# Rocketometer2148_MPU9150_GPS_No_Osc.net
KiCad netlist of a schematic drawn in EAGLE
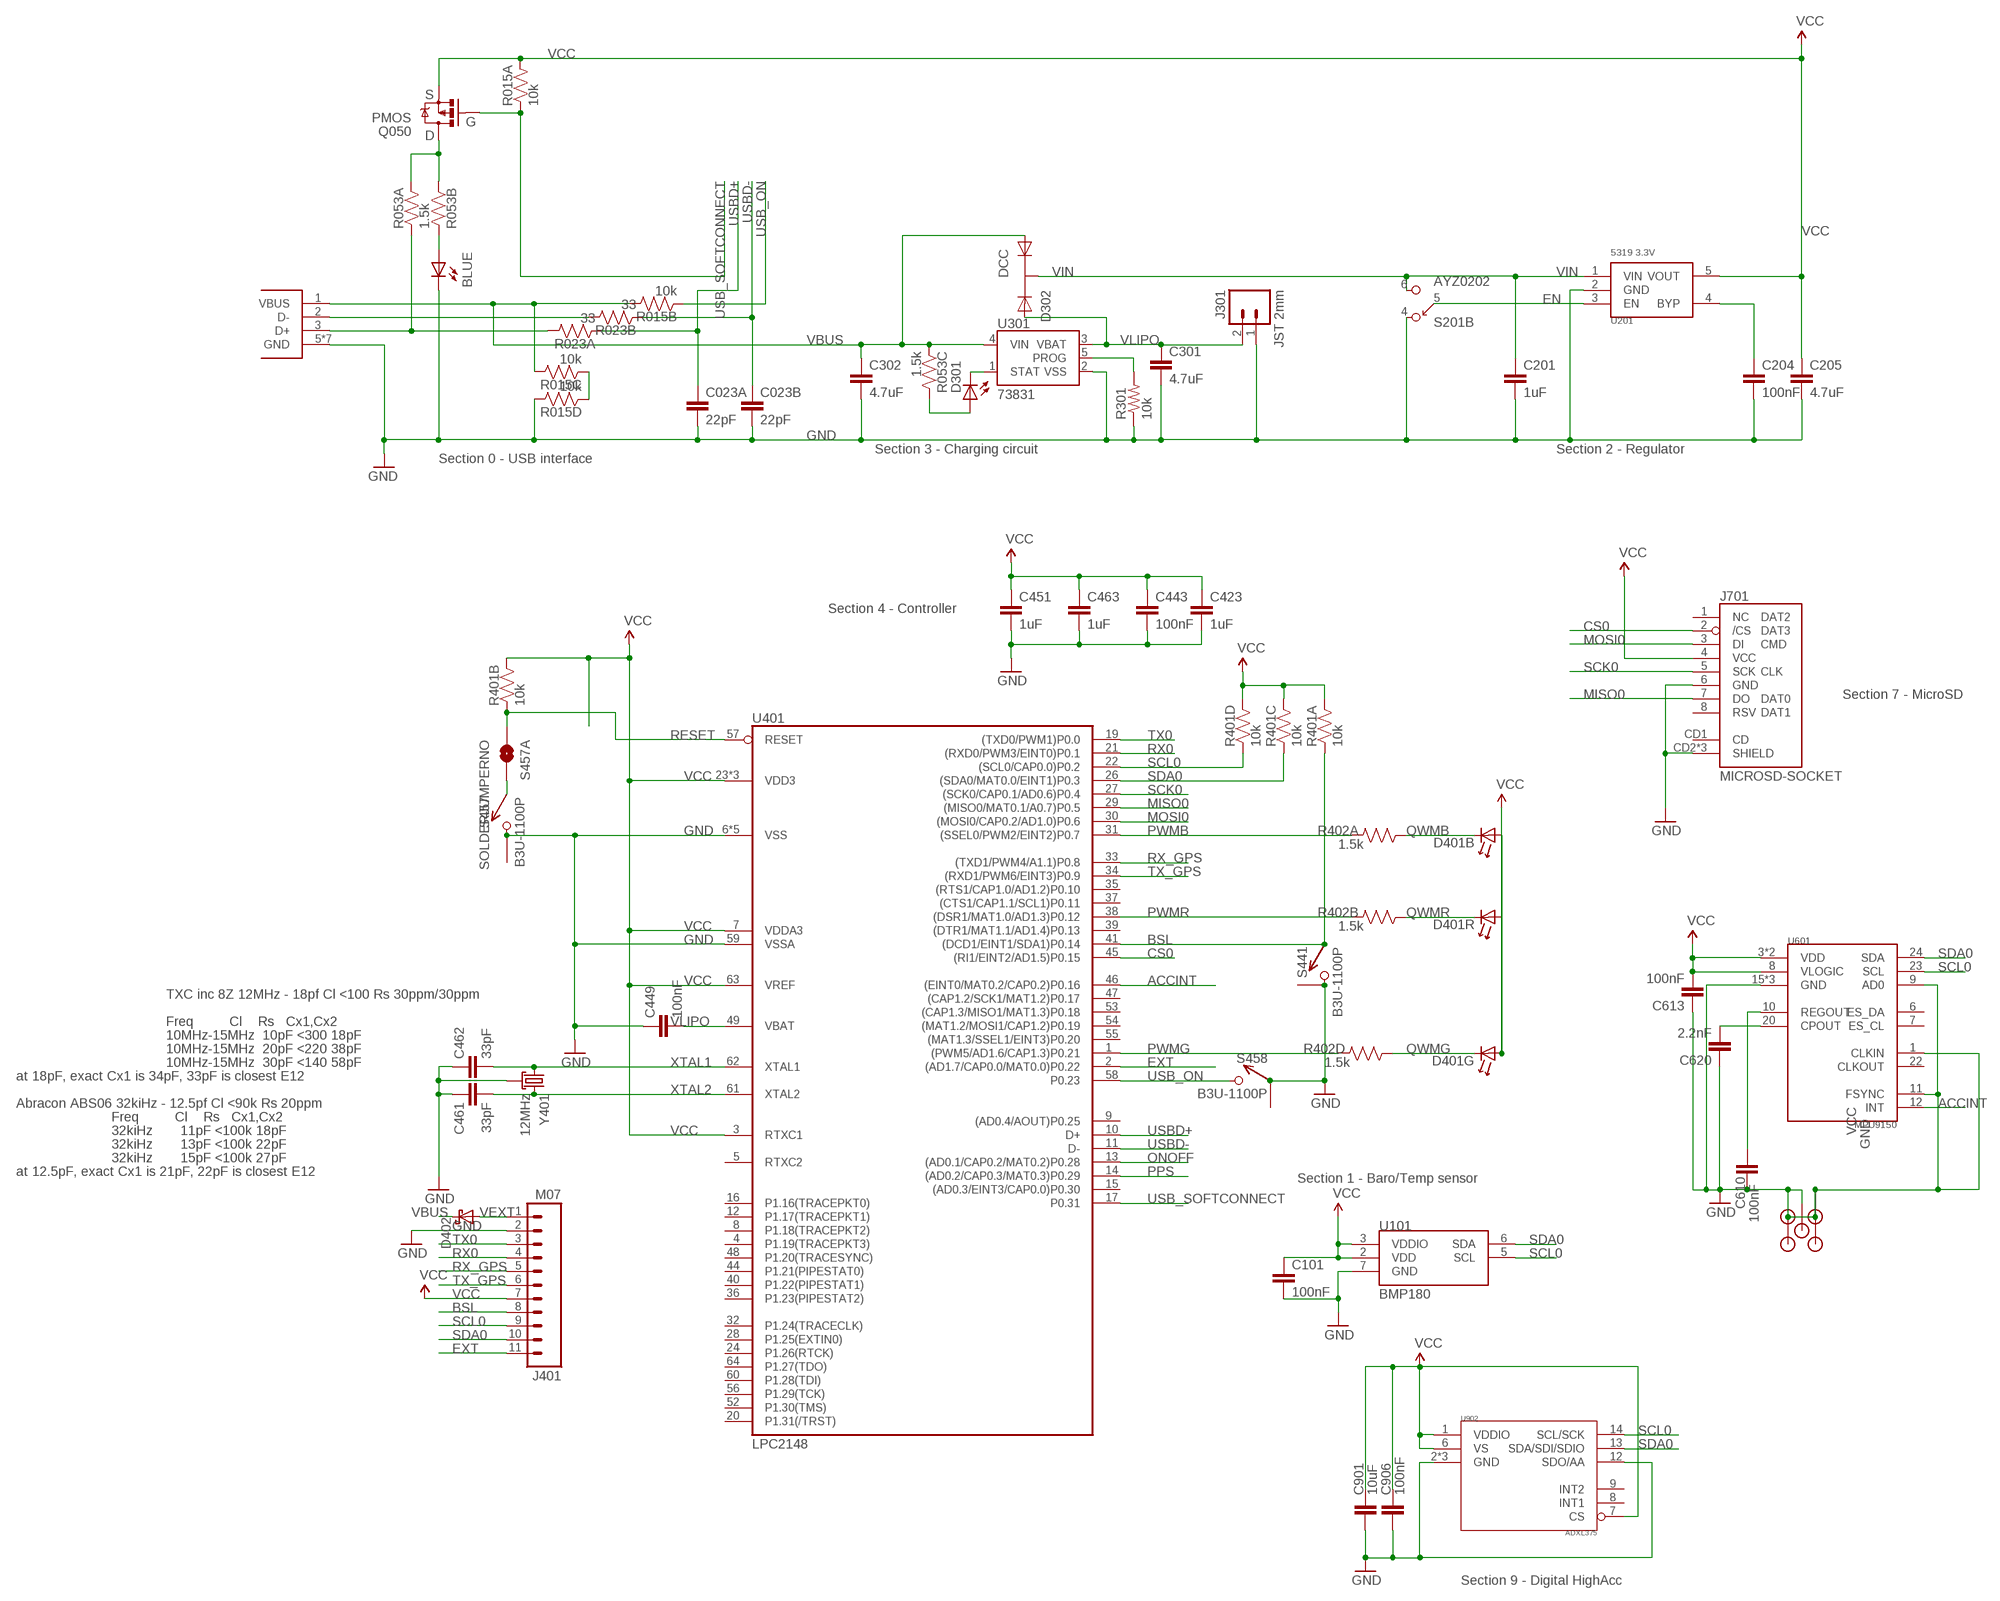
[diagram p0: schematic, sheet 1, part 1 of 2]
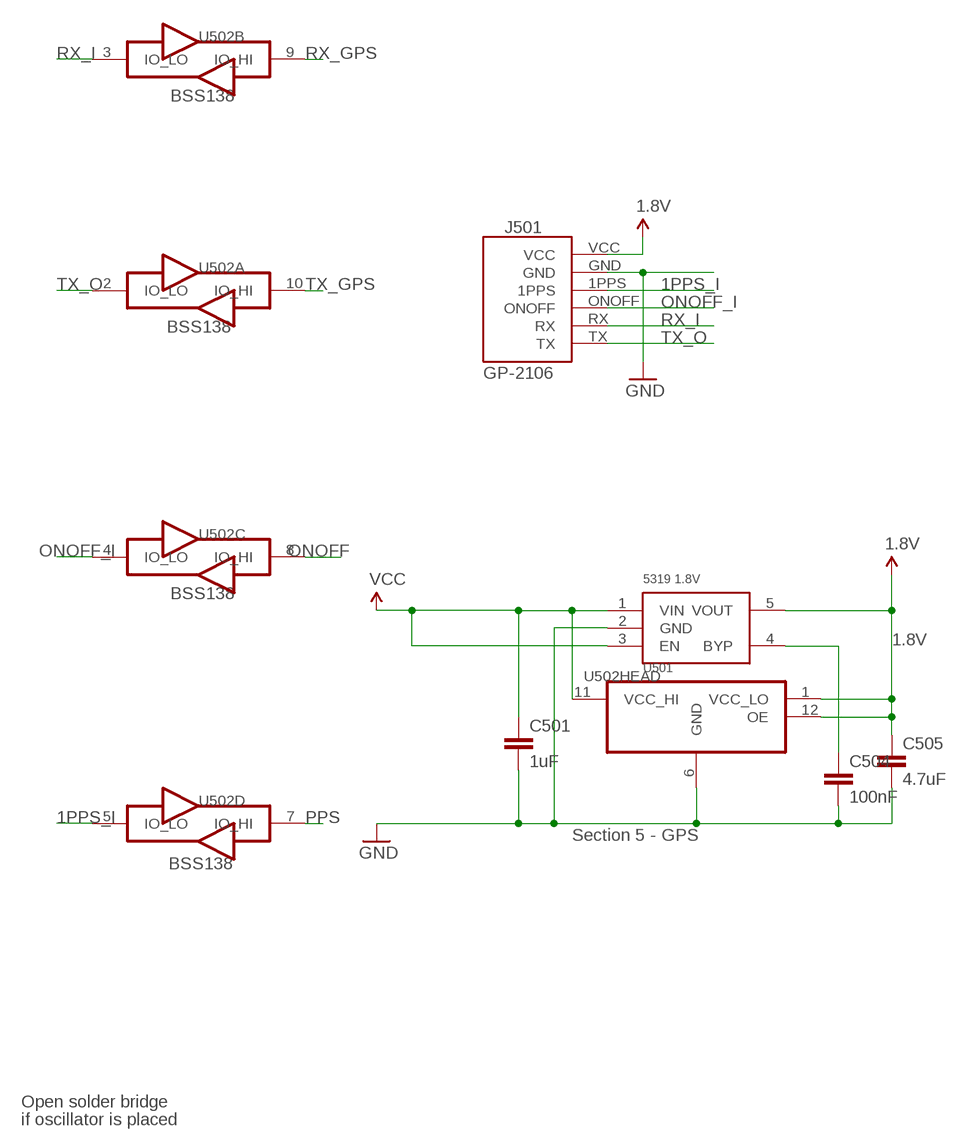
[diagram p1: schematic, sheet 1, part 2 of 2]

(export (version "E")
  (design (tool "Eeschema 10.0.6"))
  (components
    (comp (ref "C023")
      (value "22pF")
      (footprint "eagle-import:CKCM25")
      (fields (field (name "DIGIKEY") "445-1860-1-ND"))
      (libsource (lib "eagle-import") (part "CKCM25"))
    )
    (comp (ref "C101")
      (value "100nF")
      (footprint "eagle-import:0402-CAP")
      (libsource (lib "eagle-import") (part "CAP0402-CAP"))
    )
    (comp (ref "C201")
      (value "1uF")
      (footprint "eagle-import:0402-CAP")
      (libsource (lib "eagle-import") (part "CAP0402-CAP"))
    )
    (comp (ref "C204")
      (value "100nF")
      (footprint "eagle-import:0402-CAP")
      (libsource (lib "eagle-import") (part "CAP0402-CAP"))
    )
    (comp (ref "C205")
      (value "4.7uF")
      (footprint "eagle-import:0402-CAP")
      (libsource (lib "eagle-import") (part "CAP0402-CAP"))
    )
    (comp (ref "C301")
      (value "4.7uF")
      (footprint "eagle-import:0402-CAP")
      (libsource (lib "eagle-import") (part "CAP0402-CAP"))
    )
    (comp (ref "C302")
      (value "4.7uF")
      (footprint "eagle-import:0402-CAP")
      (libsource (lib "eagle-import") (part "CAP0402-CAP"))
    )
    (comp (ref "C423")
      (value "1uF")
      (footprint "eagle-import:0402-CAP")
      (libsource (lib "eagle-import") (part "CAP0402-CAP"))
    )
    (comp (ref "C443")
      (value "100nF")
      (footprint "eagle-import:0402-CAP")
      (libsource (lib "eagle-import") (part "CAP0402-CAP"))
    )
    (comp (ref "C449")
      (value "100nF")
      (footprint "eagle-import:0402-CAP")
      (libsource (lib "eagle-import") (part "CAP0402-CAP"))
    )
    (comp (ref "C451")
      (value "1uF")
      (footprint "eagle-import:0402-CAP")
      (libsource (lib "eagle-import") (part "CAP0402-CAP"))
    )
    (comp (ref "C461")
      (value "33pF")
      (footprint "eagle-import:0402-CAP")
      (libsource (lib "eagle-import") (part "CAP0402-CAP"))
    )
    (comp (ref "C462")
      (value "33pF")
      (footprint "eagle-import:0402-CAP")
      (libsource (lib "eagle-import") (part "CAP0402-CAP"))
    )
    (comp (ref "C463")
      (value "1uF")
      (footprint "eagle-import:0402-CAP")
      (libsource (lib "eagle-import") (part "CAP0402-CAP"))
    )
    (comp (ref "C501")
      (value "1uF")
      (footprint "eagle-import:0402-CAP")
      (libsource (lib "eagle-import") (part "CAP0402-CAP"))
    )
    (comp (ref "C504")
      (value "100nF")
      (footprint "eagle-import:0402-CAP")
      (libsource (lib "eagle-import") (part "CAP0402-CAP"))
    )
    (comp (ref "C505")
      (value "4.7uF")
      (footprint "eagle-import:0402-CAP")
      (libsource (lib "eagle-import") (part "CAP0402-CAP"))
    )
    (comp (ref "C610")
      (value "100nF")
      (footprint "eagle-import:0402-CAP")
      (libsource (lib "eagle-import") (part "CAP0402-CAP"))
    )
    (comp (ref "C613")
      (value "100nF")
      (footprint "eagle-import:0402-CAP")
      (libsource (lib "eagle-import") (part "CAP0402-CAP"))
    )
    (comp (ref "C620")
      (value "2.2nF")
      (footprint "eagle-import:0402-CAP")
      (libsource (lib "eagle-import") (part "CAP0402-CAP"))
    )
    (comp (ref "C901")
      (value "10uF")
      (footprint "eagle-import:0603-CAP")
      (libsource (lib "eagle-import") (part "CAP0603-CAP"))
    )
    (comp (ref "C906")
      (value "100nF")
      (footprint "eagle-import:0402-CAP")
      (libsource (lib "eagle-import") (part "SparkFun-Passives_CAP0402-CAP"))
    )
    (comp (ref "D050")
      (value "BLUE")
      (footprint "eagle-import:LED-0603")
      (libsource (lib "eagle-import") (part "LED0603"))
    )
    (comp (ref "D301")
      (value "YELLOW")
      (footprint "eagle-import:LED-0603")
      (libsource (lib "eagle-import") (part "LED0603"))
    )
    (comp (ref "D302")
      (value "DCC")
      (footprint "eagle-import:SOT-23-3")
      (libsource (lib "eagle-import") (part "PMEG2005CT"))
    )
    (comp (ref "D401")
      (value "SMLP36RGB2W(R)")
      (footprint "eagle-import:SMLP36")
      (fields (field (name "DIGIKEY") "846-1097-1-ND"))
      (libsource (lib "eagle-import") (part "SMLP36RGB2W(R)"))
    )
    (comp (ref "D402")
      (value "DIODE_SCHOTTKY")
      (footprint "eagle-import:D0603")
      (libsource (lib "eagle-import") (part "DIODE_SCHOTTKY"))
    )
    (comp (ref "J001")
      (value "USB_MICROB_JSTGCT")
      (footprint "eagle-import:USB_MICROB_3075")
      (libsource (lib "eagle-import") (part "USB_MICROB_JSTGCT"))
    )
    (comp (ref "J301")
      (value "JST 2mm")
      (footprint "eagle-import:JST-2-SMD")
      (libsource (lib "eagle-import") (part "M02-JST-2MM-SMT"))
    )
    (comp (ref "J401")
      (value "M07")
      (footprint "eagle-import:1X11")
      (libsource (lib "eagle-import") (part "M11PTH"))
    )
    (comp (ref "J501")
      (value "GP-2106")
      (footprint "eagle-import:GP-2106")
      (libsource (lib "eagle-import") (part "GP-2106"))
    )
    (comp (ref "J701")
      (value "MICROSD-SOCKET")
      (footprint "eagle-import:MICROSD-SOCKET-PP")
      (libsource (lib "eagle-import") (part "MICROSD-SOCKET"))
    )
    (comp (ref "JP1")
      (value "STANDOFF")
      (footprint "eagle-import:STANDOFF")
      (libsource (lib "eagle-import") (part "STANDOFF"))
    )
    (comp (ref "JP2")
      (value "STANDOFF")
      (footprint "eagle-import:STANDOFF")
      (libsource (lib "eagle-import") (part "STANDOFF"))
    )
    (comp (ref "JP3")
      (value "STANDOFF")
      (footprint "eagle-import:STANDOFF")
      (libsource (lib "eagle-import") (part "STANDOFF"))
    )
    (comp (ref "JP4")
      (value "STANDOFF")
      (footprint "eagle-import:STANDOFF")
      (libsource (lib "eagle-import") (part "STANDOFF"))
    )
    (comp (ref "JP5")
      (value "STANDOFF")
      (footprint "eagle-import:STANDOFF")
      (libsource (lib "eagle-import") (part "STANDOFF"))
    )
    (comp (ref "Q050")
      (value "PMOS")
      (footprint "eagle-import:SOT23-3")
      (libsource (lib "eagle-import") (part "MOSFET-PCHANNELSMD"))
    )
    (comp (ref "R015")
      (value "10k")
      (footprint "eagle-import:CRA04")
      (fields (field (name "DIGIKEY") "Y5103CT-ND"))
      (libsource (lib "eagle-import") (part "RP404"))
    )
    (comp (ref "R023")
      (value "33")
      (footprint "eagle-import:CRA02")
      (libsource (lib "eagle-import") (part "RP2EXB24V"))
    )
    (comp (ref "R053")
      (value "1.5k")
      (footprint "eagle-import:CRA04")
      (fields (field (name "DIGIKEY") "CRA4S81.5KCT-ND"))
      (libsource (lib "eagle-import") (part "RP404"))
    )
    (comp (ref "R301")
      (value "10k")
      (footprint "eagle-import:0402-RES")
      (libsource (lib "eagle-import") (part "RESISTOR0402-RES"))
    )
    (comp (ref "R401")
      (value "10k")
      (footprint "eagle-import:CRA04")
      (fields (field (name "DIGIKEY") "CRA4S810KCT-ND"))
      (libsource (lib "eagle-import") (part "RP404"))
    )
    (comp (ref "R402")
      (value "1.5k")
      (footprint "eagle-import:CRA04")
      (fields (field (name "DIGIKEY") "CRA4S81.5KCT-ND"))
      (libsource (lib "eagle-import") (part "RP404"))
    )
    (comp (ref "S201")
      (value "AYZ0202")
      (footprint "eagle-import:AYZ0202")
      (libsource (lib "eagle-import") (part "AYZ0202"))
    )
    (comp (ref "S441")
      (value "B3U-1100P")
      (footprint "eagle-import:B3U-1100P")
      (fields (field (name "DIGIKEY") "SW1021CT-ND"))
      (libsource (lib "eagle-import") (part "B3U-1100P"))
    )
    (comp (ref "S457")
      (value "B3U-1100P")
      (footprint "eagle-import:B3U-1100P")
      (fields (field (name "DIGIKEY") "SW1021CT-ND"))
      (libsource (lib "eagle-import") (part "B3U-1100P"))
    )
    (comp (ref "S457A")
      (value "SOLDERJUMPERNO")
      (footprint "eagle-import:SJ_2S-NO")
      (libsource (lib "eagle-import") (part "SOLDERJUMPERNO"))
    )
    (comp (ref "S458")
      (value "B3U-1100P")
      (footprint "eagle-import:B3U-1100P")
      (fields (field (name "DIGIKEY") "SW1021CT-ND"))
      (libsource (lib "eagle-import") (part "B3U-1100P"))
    )
    (comp (ref "U101")
      (value "BMP180")
      (footprint "eagle-import:BMP180")
      (libsource (lib "eagle-import") (part "BMP180"))
    )
    (comp (ref "U201")
      (value "5319 3.3V")
      (footprint "eagle-import:SOT-23-5")
      (libsource (lib "eagle-import") (part "MIC5319D5"))
    )
    (comp (ref "U301")
      (value "73831")
      (footprint "eagle-import:SOT23-5")
      (libsource (lib "eagle-import") (part "MCP73831"))
    )
    (comp (ref "U401")
      (value "LPC2148")
      (footprint "eagle-import:LQFP64")
      (libsource (lib "eagle-import") (part "LPC2148"))
    )
    (comp (ref "U501")
      (value "5319 1.8V")
      (footprint "eagle-import:SOT-23-5")
      (libsource (lib "eagle-import") (part "MIC5319D5"))
    )
    (comp (ref "U502")
      (value "TXB0104RUT")
      (footprint "eagle-import:R-PUQFN-N12")
      (libsource (lib "eagle-import") (part "TXB0104RUT"))
    )
    (comp (ref "U601")
      (value "MPU9150")
      (footprint "eagle-import:LLGA24")
      (libsource (lib "eagle-import") (part "MPU9150"))
    )
    (comp (ref "U902")
      (value "ADXL375")
      (footprint "eagle-import:ADXL375")
      (libsource (lib "eagle-import") (part "ADXL375"))
    )
    (comp (ref "Y401")
      (value "12MHz")
      (footprint "eagle-import:CRYSTAL_SMD_2MM_2_5MM")
      (libsource (lib "eagle-import") (part "CX2520"))
    )
  )
  (nets
    (net (code "1") (name "/1PPS_I") (class "Default")
      (node (ref "J501") (pin "1PPS") (pinfunction "1PPS_1PPS") (pintype "bidirectional"))
      (node (ref "U502") (pin "5") (pinfunction "IO_LO_5") (pintype "bidirectional"))
    )
    (net (code "2") (name "/ACCINT") (class "Default")
      (node (ref "U401") (pin "46") (pinfunction "(EINT0/MAT0.2/CAP0.2)P0.16_46") (pintype "bidirectional"))
      (node (ref "U601") (pin "12") (pinfunction "INT_12") (pintype "bidirectional"))
    )
    (net (code "3") (name "/BSL") (class "Default")
      (node (ref "J401") (pin "8") (pinfunction "8_8") (pintype "passive"))
      (node (ref "R401") (pin "1") (pinfunction "1_1") (pintype "passive"))
      (node (ref "S441") (pin "P$1") (pinfunction "1_P$1") (pintype "bidirectional"))
      (node (ref "U401") (pin "41") (pinfunction "(DCD1/EINT1/SDA1)P0.14_41") (pintype "bidirectional"))
    )
    (net (code "4") (name "/CS0") (class "Default")
      (node (ref "J701") (pin "2") (pinfunction "/CS_2") (pintype "bidirectional"))
      (node (ref "U401") (pin "45") (pinfunction "(RI1/EINT2/AD1.5)P0.15_45") (pintype "bidirectional"))
    )
    (net (code "5") (name "/EN") (class "Default")
      (node (ref "S201") (pin "5") (pinfunction "P$3_5") (pintype "bidirectional"))
      (node (ref "U201") (pin "3") (pinfunction "EN_3") (pintype "bidirectional"))
    )
    (net (code "6") (name "/EXT") (class "Default")
      (node (ref "J401") (pin "11") (pinfunction "11_11") (pintype "passive"))
      (node (ref "U401") (pin "2") (pinfunction "(AD1.7/CAP0.0/MAT0.0)P0.22_2") (pintype "bidirectional"))
    )
    (net (code "7") (name "/MISO0") (class "Default")
      (node (ref "J701") (pin "7") (pinfunction "DO_7") (pintype "bidirectional"))
      (node (ref "U401") (pin "29") (pinfunction "(MISO0/MAT0.1/A0.7)P0.5_29") (pintype "bidirectional"))
    )
    (net (code "8") (name "/MOSI0") (class "Default")
      (node (ref "J701") (pin "3") (pinfunction "DI_3") (pintype "bidirectional"))
      (node (ref "U401") (pin "30") (pinfunction "(MOSI0/CAP0.2/AD1.0)P0.6_30") (pintype "bidirectional"))
    )
    (net (code "9") (name "/ONOFF") (class "Default")
      (node (ref "U401") (pin "13") (pinfunction "(AD0.1/CAP0.2/MAT0.2)P0.28_13") (pintype "bidirectional"))
      (node (ref "U502") (pin "8") (pinfunction "IO_HI_8") (pintype "bidirectional"))
    )
    (net (code "10") (name "/ONOFF_I") (class "Default")
      (node (ref "J501") (pin "ONOFF") (pinfunction "ONOFF_ONOFF") (pintype "bidirectional"))
      (node (ref "U502") (pin "4") (pinfunction "IO_LO_4") (pintype "bidirectional"))
    )
    (net (code "11") (name "/PPS") (class "Default")
      (node (ref "U401") (pin "14") (pinfunction "(AD0.2/CAP0.3/MAT0.3)P0.29_14") (pintype "bidirectional"))
      (node (ref "U502") (pin "7") (pinfunction "IO_HI_7") (pintype "bidirectional"))
    )
    (net (code "12") (name "/PWMB") (class "Default")
      (node (ref "R402") (pin "8") (pinfunction "2_8") (pintype "passive"))
      (node (ref "U401") (pin "31") (pinfunction "(SSEL0/PWM2/EINT2)P0.7_31") (pintype "bidirectional"))
    )
    (net (code "13") (name "/PWMG") (class "Default")
      (node (ref "R402") (pin "5") (pinfunction "2_5") (pintype "passive"))
      (node (ref "U401") (pin "1") (pinfunction "(PWM5/AD1.6/CAP1.3)P0.21_1") (pintype "bidirectional"))
    )
    (net (code "14") (name "/PWMR") (class "Default")
      (node (ref "R402") (pin "7") (pinfunction "2_7") (pintype "passive"))
      (node (ref "U401") (pin "38") (pinfunction "(DSR1/MAT1.0/AD1.3)P0.12_38") (pintype "bidirectional"))
    )
    (net (code "15") (name "/QWMB") (class "Default")
      (node (ref "D401") (pin "1") (pinfunction "C_1") (pintype "passive"))
      (node (ref "R402") (pin "1") (pinfunction "1_1") (pintype "passive"))
    )
    (net (code "16") (name "/QWMG") (class "Default")
      (node (ref "D401") (pin "5") (pinfunction "C_5") (pintype "passive"))
      (node (ref "R402") (pin "4") (pinfunction "1_4") (pintype "passive"))
    )
    (net (code "17") (name "/QWMR") (class "Default")
      (node (ref "D401") (pin "3") (pinfunction "C_3") (pintype "passive"))
      (node (ref "R402") (pin "2") (pinfunction "1_2") (pintype "passive"))
    )
    (net (code "18") (name "/RESET") (class "Default")
      (node (ref "R401") (pin "2") (pinfunction "1_2") (pintype "passive"))
      (node (ref "S457A") (pin "1") (pinfunction "1_1") (pintype "passive"))
      (node (ref "U401") (pin "57") (pinfunction "RESET_57") (pintype "input"))
    )
    (net (code "19") (name "/RX0") (class "Default")
      (node (ref "J401") (pin "4") (pinfunction "4_4") (pintype "passive"))
      (node (ref "U401") (pin "21") (pinfunction "(RXD0/PWM3/EINT0)P0.1_21") (pintype "bidirectional"))
    )
    (net (code "20") (name "/RX_GPS") (class "Default")
      (node (ref "J401") (pin "5") (pinfunction "5_5") (pintype "passive"))
      (node (ref "U401") (pin "33") (pinfunction "(TXD1/PWM4/A1.1)P0.8_33") (pintype "bidirectional"))
      (node (ref "U502") (pin "9") (pinfunction "IO_HI_9") (pintype "bidirectional"))
    )
    (net (code "21") (name "/RX_I") (class "Default")
      (node (ref "J501") (pin "RX") (pinfunction "RX_RX") (pintype "bidirectional"))
      (node (ref "U502") (pin "3") (pinfunction "IO_LO_3") (pintype "bidirectional"))
    )
    (net (code "22") (name "/SCK0") (class "Default")
      (node (ref "J701") (pin "5") (pinfunction "SCK_5") (pintype "bidirectional"))
      (node (ref "U401") (pin "27") (pinfunction "(SCK0/CAP0.1/AD0.6)P0.4_27") (pintype "bidirectional"))
    )
    (net (code "23") (name "/SCL0") (class "Default")
      (node (ref "J401") (pin "9") (pinfunction "9_9") (pintype "passive"))
      (node (ref "R401") (pin "4") (pinfunction "1_4") (pintype "passive"))
      (node (ref "U101") (pin "5") (pinfunction "SCL_5") (pintype "input"))
      (node (ref "U401") (pin "22") (pinfunction "(SCL0/CAP0.0)P0.2_22") (pintype "bidirectional"))
      (node (ref "U601") (pin "23") (pinfunction "SCL_23") (pintype "bidirectional"))
      (node (ref "U902") (pin "14") (pinfunction "SCL/SCK_14") (pintype "input"))
    )
    (net (code "24") (name "/SDA0") (class "Default")
      (node (ref "J401") (pin "10") (pinfunction "10_10") (pintype "passive"))
      (node (ref "R401") (pin "3") (pinfunction "1_3") (pintype "passive"))
      (node (ref "U101") (pin "6") (pinfunction "SDA_6") (pintype "bidirectional"))
      (node (ref "U401") (pin "26") (pinfunction "(SDA0/MAT0.0/EINT1)P0.3_26") (pintype "bidirectional"))
      (node (ref "U601") (pin "24") (pinfunction "SDA_24") (pintype "bidirectional"))
      (node (ref "U902") (pin "13") (pinfunction "SDA/SDI/SDIO_13") (pintype "bidirectional"))
    )
    (net (code "25") (name "/TX0") (class "Default")
      (node (ref "J401") (pin "3") (pinfunction "3_3") (pintype "passive"))
      (node (ref "U401") (pin "19") (pinfunction "(TXD0/PWM1)P0.0_19") (pintype "bidirectional"))
    )
    (net (code "26") (name "/TX_GPS") (class "Default")
      (node (ref "J401") (pin "6") (pinfunction "6_6") (pintype "passive"))
      (node (ref "U401") (pin "34") (pinfunction "(RXD1/PWM6/EINT3)P0.9_34") (pintype "bidirectional"))
      (node (ref "U502") (pin "10") (pinfunction "IO_HI_10") (pintype "bidirectional"))
    )
    (net (code "27") (name "/TX_O") (class "Default")
      (node (ref "J501") (pin "TX") (pinfunction "TX_TX") (pintype "bidirectional"))
      (node (ref "U502") (pin "2") (pinfunction "IO_LO_2") (pintype "bidirectional"))
    )
    (net (code "28") (name "/USBD+") (class "Default")
      (node (ref "C023") (pin "1") (pinfunction "1_1") (pintype "passive"))
      (node (ref "R023") (pin "1") (pinfunction "1_1") (pintype "passive"))
      (node (ref "U401") (pin "10") (pinfunction "D+_10") (pintype "bidirectional"))
    )
    (net (code "29") (name "/USBD-") (class "Default")
      (node (ref "C023") (pin "2") (pinfunction "1_2") (pintype "passive"))
      (node (ref "R023") (pin "2") (pinfunction "1_2") (pintype "passive"))
      (node (ref "U401") (pin "11") (pinfunction "D-_11") (pintype "bidirectional"))
    )
    (net (code "30") (name "/USB_ON") (class "Default")
      (node (ref "R015") (pin "2") (pinfunction "1_2") (pintype "passive"))
      (node (ref "S458") (pin "P$2") (pinfunction "2_P$2") (pintype "bidirectional"))
      (node (ref "U401") (pin "58") (pinfunction "P0.23_58") (pintype "bidirectional"))
    )
    (net (code "31") (name "/USB_SOFTCONNECT") (class "Default")
      (node (ref "Q050") (pin "1") (pinfunction "G_1") (pintype "passive"))
      (node (ref "R015") (pin "1") (pinfunction "1_1") (pintype "passive"))
      (node (ref "U401") (pin "17") (pinfunction "P0.31_17") (pintype "output"))
    )
    (net (code "32") (name "/VBUS") (class "Default")
      (node (ref "C302") (pin "1") (pinfunction "1_1") (pintype "passive"))
      (node (ref "D302") (pin "1") (pinfunction "A1_1") (pintype "passive"))
      (node (ref "D402") (pin "C") (pinfunction "K_C") (pintype "passive"))
      (node (ref "J001") (pin "1") (pinfunction "VBUS_1") (pintype "bidirectional"))
      (node (ref "R015") (pin "6") (pinfunction "2_6") (pintype "passive"))
      (node (ref "R015") (pin "7") (pinfunction "2_7") (pintype "passive"))
      (node (ref "R053") (pin "3") (pinfunction "1_3") (pintype "passive"))
      (node (ref "U301") (pin "4") (pinfunction "VIN_4") (pintype "power_in"))
    )
    (net (code "33") (name "/VEXT") (class "Default")
      (node (ref "D402") (pin "A") (pinfunction "A_A") (pintype "passive"))
      (node (ref "J401") (pin "1") (pinfunction "1_1") (pintype "passive"))
    )
    (net (code "34") (name "/VIN") (class "Default")
      (node (ref "C201") (pin "1") (pinfunction "1_1") (pintype "passive"))
      (node (ref "D302") (pin "3") (pinfunction "K_3") (pintype "passive"))
      (node (ref "S201") (pin "6") (pinfunction "P$2_6") (pintype "bidirectional"))
      (node (ref "U201") (pin "1") (pinfunction "VIN_1") (pintype "bidirectional"))
    )
    (net (code "35") (name "/VLIPO") (class "Default")
      (node (ref "C301") (pin "1") (pinfunction "1_1") (pintype "passive"))
      (node (ref "C449") (pin "2") (pinfunction "2_2") (pintype "passive"))
      (node (ref "D302") (pin "2") (pinfunction "A2_2") (pintype "passive"))
      (node (ref "J301") (pin "2") (pinfunction "2_2") (pintype "passive"))
      (node (ref "U301") (pin "3") (pinfunction "VBAT_3") (pintype "power_in"))
      (node (ref "U401") (pin "49") (pinfunction "VBAT_49") (pintype "power_in"))
    )
    (net (code "36") (name "/XTAL1") (class "Default")
      (node (ref "C462") (pin "2") (pinfunction "2_2") (pintype "passive"))
      (node (ref "U401") (pin "62") (pinfunction "XTAL1_62") (pintype "input"))
      (node (ref "Y401") (pin "1") (pinfunction "1_1") (pintype "passive"))
    )
    (net (code "37") (name "/XTAL2") (class "Default")
      (node (ref "C461") (pin "2") (pinfunction "2_2") (pintype "passive"))
      (node (ref "U401") (pin "61") (pinfunction "XTAL2_61") (pintype "output"))
      (node (ref "Y401") (pin "3") (pinfunction "2_3") (pintype "passive"))
    )
    (net (code "38") (name "1.8V") (class "Default")
      (node (ref "C505") (pin "1") (pinfunction "1_1") (pintype "passive"))
      (node (ref "J501") (pin "VCC") (pinfunction "VCC_VCC") (pintype "bidirectional"))
      (node (ref "U501") (pin "5") (pinfunction "VOUT_5") (pintype "bidirectional"))
      (node (ref "U502") (pin "1") (pinfunction "VCC_LO_1") (pintype "power_in"))
      (node (ref "U502") (pin "12") (pinfunction "OE_12") (pintype "bidirectional"))
    )
    (net (code "39") (name "GND") (class "Default")
      (node (ref "C023") (pin "3") (pinfunction "2_3") (pintype "passive"))
      (node (ref "C023") (pin "4") (pinfunction "2_4") (pintype "passive"))
      (node (ref "C101") (pin "2") (pinfunction "2_2") (pintype "passive"))
      (node (ref "C201") (pin "2") (pinfunction "2_2") (pintype "passive"))
      (node (ref "C204") (pin "2") (pinfunction "2_2") (pintype "passive"))
      (node (ref "C205") (pin "2") (pinfunction "2_2") (pintype "passive"))
      (node (ref "C301") (pin "2") (pinfunction "2_2") (pintype "passive"))
      (node (ref "C302") (pin "2") (pinfunction "2_2") (pintype "passive"))
      (node (ref "C423") (pin "2") (pinfunction "2_2") (pintype "passive"))
      (node (ref "C443") (pin "2") (pinfunction "2_2") (pintype "passive"))
      (node (ref "C449") (pin "1") (pinfunction "1_1") (pintype "passive"))
      (node (ref "C451") (pin "2") (pinfunction "2_2") (pintype "passive"))
      (node (ref "C461") (pin "1") (pinfunction "1_1") (pintype "passive"))
      (node (ref "C462") (pin "1") (pinfunction "1_1") (pintype "passive"))
      (node (ref "C463") (pin "2") (pinfunction "2_2") (pintype "passive"))
      (node (ref "C501") (pin "2") (pinfunction "2_2") (pintype "passive"))
      (node (ref "C504") (pin "2") (pinfunction "2_2") (pintype "passive"))
      (node (ref "C505") (pin "2") (pinfunction "2_2") (pintype "passive"))
      (node (ref "C610") (pin "2") (pinfunction "2_2") (pintype "passive"))
      (node (ref "C613") (pin "1") (pinfunction "1_1") (pintype "passive"))
      (node (ref "C620") (pin "1") (pinfunction "1_1") (pintype "passive"))
      (node (ref "C901") (pin "2") (pinfunction "2_2") (pintype "passive"))
      (node (ref "C906") (pin "2") (pinfunction "2_2") (pintype "passive"))
      (node (ref "D050") (pin "C") (pinfunction "C_C") (pintype "passive"))
      (node (ref "J001") (pin "5") (pinfunction "GND_5") (pintype "bidirectional"))
      (node (ref "J001") (pin "P$1") (pinfunction "GND_P$1") (pintype "bidirectional"))
      (node (ref "J001") (pin "P$10") (pinfunction "GND_P$10") (pintype "bidirectional"))
      (node (ref "J001") (pin "P$2") (pinfunction "GND_P$2") (pintype "bidirectional"))
      (node (ref "J001") (pin "P$3") (pinfunction "GND_P$3") (pintype "bidirectional"))
      (node (ref "J001") (pin "P$4") (pinfunction "GND_P$4") (pintype "bidirectional"))
      (node (ref "J001") (pin "P$8") (pinfunction "GND_P$8") (pintype "bidirectional"))
      (node (ref "J301") (pin "1") (pinfunction "1_1") (pintype "passive"))
      (node (ref "J401") (pin "2") (pinfunction "2_2") (pintype "passive"))
      (node (ref "J501") (pin "GND") (pinfunction "GND_GND") (pintype "bidirectional"))
      (node (ref "J701") (pin "6") (pinfunction "GND_6") (pintype "bidirectional"))
      (node (ref "J701") (pin "CD2") (pinfunction "SHIELD_CD2") (pintype "bidirectional"))
      (node (ref "J701") (pin "GND1") (pinfunction "SHIELD_GND1") (pintype "bidirectional"))
      (node (ref "J701") (pin "GND3") (pinfunction "SHIELD_GND3") (pintype "bidirectional"))
      (node (ref "JP1") (pin "P$1") (pinfunction "P$1_P$1") (pintype "bidirectional"))
      (node (ref "JP2") (pin "P$1") (pinfunction "P$1_P$1") (pintype "bidirectional"))
      (node (ref "JP3") (pin "P$1") (pinfunction "P$1_P$1") (pintype "bidirectional"))
      (node (ref "JP4") (pin "P$1") (pinfunction "P$1_P$1") (pintype "bidirectional"))
      (node (ref "JP5") (pin "P$1") (pinfunction "P$1_P$1") (pintype "bidirectional"))
      (node (ref "R015") (pin "5") (pinfunction "2_5") (pintype "passive"))
      (node (ref "R301") (pin "1") (pinfunction "1_1") (pintype "passive"))
      (node (ref "S201") (pin "4") (pinfunction "P$1_4") (pintype "bidirectional"))
      (node (ref "S441") (pin "P$2") (pinfunction "2_P$2") (pintype "bidirectional"))
      (node (ref "S441") (pin "P$3") (pinfunction "1_P$3") (pintype "bidirectional"))
      (node (ref "S457") (pin "P$2") (pinfunction "2_P$2") (pintype "bidirectional"))
      (node (ref "S457") (pin "P$3") (pinfunction "1_P$3") (pintype "bidirectional"))
      (node (ref "S458") (pin "P$1") (pinfunction "1_P$1") (pintype "bidirectional"))
      (node (ref "S458") (pin "P$3") (pinfunction "1_P$3") (pintype "bidirectional"))
      (node (ref "U101") (pin "7") (pinfunction "GND_7") (pintype "power_in"))
      (node (ref "U201") (pin "2") (pinfunction "GND_2") (pintype "bidirectional"))
      (node (ref "U301") (pin "2") (pinfunction "VSS_2") (pintype "power_in"))
      (node (ref "U401") (pin "18") (pinfunction "VSS_18") (pintype "power_in"))
      (node (ref "U401") (pin "25") (pinfunction "VSS_25") (pintype "power_in"))
      (node (ref "U401") (pin "42") (pinfunction "VSS_42") (pintype "power_in"))
      (node (ref "U401") (pin "50") (pinfunction "VSS_50") (pintype "power_in"))
      (node (ref "U401") (pin "59") (pinfunction "VSSA_59") (pintype "power_in"))
      (node (ref "U401") (pin "6") (pinfunction "VSS_6") (pintype "power_in"))
      (node (ref "U501") (pin "2") (pinfunction "GND_2") (pintype "bidirectional"))
      (node (ref "U502") (pin "6") (pinfunction "GND_6") (pintype "power_in"))
      (node (ref "U601") (pin "1") (pinfunction "CLKIN_1") (pintype "bidirectional"))
      (node (ref "U601") (pin "11") (pinfunction "FSYNC_11") (pintype "bidirectional"))
      (node (ref "U601") (pin "15") (pinfunction "GND_15") (pintype "bidirectional"))
      (node (ref "U601") (pin "17") (pinfunction "GND_17") (pintype "bidirectional"))
      (node (ref "U601") (pin "18") (pinfunction "GND_18") (pintype "bidirectional"))
      (node (ref "U601") (pin "9") (pinfunction "AD0_9") (pintype "bidirectional"))
      (node (ref "U902") (pin "12") (pinfunction "SDO/AA_12") (pintype "bidirectional"))
      (node (ref "U902") (pin "2") (pinfunction "GND_2") (pintype "power_in"))
      (node (ref "U902") (pin "4") (pinfunction "GND_4") (pintype "power_in"))
      (node (ref "U902") (pin "5") (pinfunction "GND_5") (pintype "power_in"))
      (node (ref "Y401") (pin "2") (pinfunction "GND_2") (pintype "passive"))
      (node (ref "Y401") (pin "4") (pinfunction "GND_4") (pintype "passive"))
    )
    (net (code "40") (name "Net-(J001-D+)") (class "Default")
      (node (ref "J001") (pin "3") (pinfunction "D+_3") (pintype "bidirectional"))
      (node (ref "R023") (pin "4") (pinfunction "2_4") (pintype "passive"))
      (node (ref "R053") (pin "1") (pinfunction "1_1") (pintype "passive"))
    )
    (net (code "41") (name "Net-(J001-D-)") (class "Default")
      (node (ref "J001") (pin "2") (pinfunction "D-_2") (pintype "bidirectional"))
      (node (ref "R023") (pin "3") (pinfunction "2_3") (pintype "passive"))
    )
    (net (code "42") (name "Net-(Q050-D)") (class "Default")
      (node (ref "Q050") (pin "3") (pinfunction "D_3") (pintype "passive"))
      (node (ref "R053") (pin "2") (pinfunction "1_2") (pintype "passive"))
      (node (ref "R053") (pin "8") (pinfunction "2_8") (pintype "passive"))
    )
    (net (code "43") (name "Net-(R015C-1)") (class "Default")
      (node (ref "R015") (pin "3") (pinfunction "1_3") (pintype "passive"))
      (node (ref "R015") (pin "4") (pinfunction "1_4") (pintype "passive"))
    )
    (net (code "44") (name "Net-(R053B-2)") (class "Default")
      (node (ref "D050") (pin "A") (pinfunction "A_A") (pintype "passive"))
      (node (ref "R053") (pin "7") (pinfunction "2_7") (pintype "passive"))
    )
    (net (code "45") (name "Net-(R053C-2)") (class "Default")
      (node (ref "D301") (pin "A") (pinfunction "A_A") (pintype "passive"))
      (node (ref "R053") (pin "6") (pinfunction "2_6") (pintype "passive"))
    )
    (net (code "46") (name "Net-(S457B-1)") (class "Default")
      (node (ref "S457") (pin "P$1") (pinfunction "1_P$1") (pintype "bidirectional"))
      (node (ref "S457A") (pin "2") (pinfunction "2_2") (pintype "passive"))
    )
    (net (code "47") (name "Net-(U201-BYP)") (class "Default")
      (node (ref "C204") (pin "1") (pinfunction "1_1") (pintype "passive"))
      (node (ref "U201") (pin "4") (pinfunction "BYP_4") (pintype "bidirectional"))
    )
    (net (code "48") (name "Net-(U301-PROG)") (class "Default")
      (node (ref "R301") (pin "2") (pinfunction "2_2") (pintype "passive"))
      (node (ref "U301") (pin "5") (pinfunction "PROG_5") (pintype "input"))
    )
    (net (code "49") (name "Net-(U301-STAT)") (class "Default")
      (node (ref "D301") (pin "C") (pinfunction "C_C") (pintype "passive"))
      (node (ref "U301") (pin "1") (pinfunction "STAT_1") (pintype "output"))
    )
    (net (code "50") (name "Net-(U501-BYP)") (class "Default")
      (node (ref "C504") (pin "1") (pinfunction "1_1") (pintype "passive"))
      (node (ref "U501") (pin "4") (pinfunction "BYP_4") (pintype "bidirectional"))
    )
    (net (code "51") (name "Net-(U601-CPOUT)") (class "Default")
      (node (ref "C620") (pin "2") (pinfunction "2_2") (pintype "passive"))
      (node (ref "U601") (pin "20") (pinfunction "CPOUT_20") (pintype "bidirectional"))
    )
    (net (code "52") (name "Net-(U601-REGOUT)") (class "Default")
      (node (ref "C610") (pin "1") (pinfunction "1_1") (pintype "passive"))
      (node (ref "U601") (pin "10") (pinfunction "REGOUT_10") (pintype "bidirectional"))
    )
    (net (code "53") (name "VCC") (class "Default")
      (node (ref "C101") (pin "1") (pinfunction "1_1") (pintype "passive"))
      (node (ref "C205") (pin "1") (pinfunction "1_1") (pintype "passive"))
      (node (ref "C423") (pin "1") (pinfunction "1_1") (pintype "passive"))
      (node (ref "C443") (pin "1") (pinfunction "1_1") (pintype "passive"))
      (node (ref "C451") (pin "1") (pinfunction "1_1") (pintype "passive"))
      (node (ref "C463") (pin "1") (pinfunction "1_1") (pintype "passive"))
      (node (ref "C501") (pin "1") (pinfunction "1_1") (pintype "passive"))
      (node (ref "C613") (pin "2") (pinfunction "2_2") (pintype "passive"))
      (node (ref "C901") (pin "1") (pinfunction "1_1") (pintype "passive"))
      (node (ref "C906") (pin "1") (pinfunction "1_1") (pintype "passive"))
      (node (ref "D401") (pin "2") (pinfunction "A_2") (pintype "passive"))
      (node (ref "D401") (pin "4") (pinfunction "A_4") (pintype "passive"))
      (node (ref "D401") (pin "6") (pinfunction "A_6") (pintype "passive"))
      (node (ref "J401") (pin "7") (pinfunction "7_7") (pintype "passive"))
      (node (ref "J701") (pin "4") (pinfunction "VCC_4") (pintype "bidirectional"))
      (node (ref "Q050") (pin "2") (pinfunction "S_2") (pintype "passive"))
      (node (ref "R015") (pin "8") (pinfunction "2_8") (pintype "passive"))
      (node (ref "R401") (pin "5") (pinfunction "2_5") (pintype "passive"))
      (node (ref "R401") (pin "6") (pinfunction "2_6") (pintype "passive"))
      (node (ref "R401") (pin "7") (pinfunction "2_7") (pintype "passive"))
      (node (ref "R401") (pin "8") (pinfunction "2_8") (pintype "passive"))
      (node (ref "U101") (pin "2") (pinfunction "VDD_2") (pintype "power_in"))
      (node (ref "U101") (pin "3") (pinfunction "VDDIO_3") (pintype "power_in"))
      (node (ref "U201") (pin "5") (pinfunction "VOUT_5") (pintype "bidirectional"))
      (node (ref "U401") (pin "23") (pinfunction "VDD3_23") (pintype "power_in"))
      (node (ref "U401") (pin "3") (pinfunction "RTXC1_3") (pintype "input"))
      (node (ref "U401") (pin "43") (pinfunction "VDD3_43") (pintype "power_in"))
      (node (ref "U401") (pin "51") (pinfunction "VDD3_51") (pintype "power_in"))
      (node (ref "U401") (pin "63") (pinfunction "VREF_63") (pintype "input"))
      (node (ref "U401") (pin "7") (pinfunction "VDDA3_7") (pintype "power_in"))
      (node (ref "U501") (pin "1") (pinfunction "VIN_1") (pintype "bidirectional"))
      (node (ref "U501") (pin "3") (pinfunction "EN_3") (pintype "bidirectional"))
      (node (ref "U502") (pin "11") (pinfunction "VCC_HI_11") (pintype "power_in"))
      (node (ref "U601") (pin "13") (pinfunction "VDD_13") (pintype "bidirectional"))
      (node (ref "U601") (pin "3") (pinfunction "VDD_3") (pintype "bidirectional"))
      (node (ref "U601") (pin "8") (pinfunction "VLOGIC_8") (pintype "bidirectional"))
      (node (ref "U902") (pin "1") (pinfunction "VDDIO_1") (pintype "power_in"))
      (node (ref "U902") (pin "6") (pinfunction "VS_6") (pintype "power_in"))
      (node (ref "U902") (pin "7") (pinfunction "CS_7") (pintype "input"))
    )
    (net (code "54") (name "unconnected-(J701-CD-PadCD1)") (class "Default")
      (node (ref "J701") (pin "CD1") (pinfunction "CD_CD1") (pintype "bidirectional"))
    )
    (net (code "55") (name "unconnected-(J701-NC-Pad1)") (class "Default")
      (node (ref "J701") (pin "1") (pinfunction "NC_1") (pintype "bidirectional"))
    )
    (net (code "56") (name "unconnected-(J701-RSV-Pad8)") (class "Default")
      (node (ref "J701") (pin "8") (pinfunction "RSV_8") (pintype "bidirectional"))
    )
    (net (code "57") (name "unconnected-(U401-(AD0.3{slash}EINT3{slash}CAP0.0)P0.30-Pad15)") (class "Default")
      (node (ref "U401") (pin "15") (pinfunction "(AD0.3/EINT3/CAP0.0)P0.30_15") (pintype "bidirectional"))
    )
    (net (code "58") (name "unconnected-(U401-(AD0.4{slash}AOUT)P0.25-Pad9)") (class "Default")
      (node (ref "U401") (pin "9") (pinfunction "(AD0.4/AOUT)P0.25_9") (pintype "bidirectional"))
    )
    (net (code "59") (name "unconnected-(U401-(CAP1.2{slash}SCK1{slash}MAT1.2)P0.17-Pad47)") (class "Default")
      (node (ref "U401") (pin "47") (pinfunction "(CAP1.2/SCK1/MAT1.2)P0.17_47") (pintype "bidirectional"))
    )
    (net (code "60") (name "unconnected-(U401-(CAP1.3{slash}MISO1{slash}MAT1.3)P0.18-Pad53)") (class "Default")
      (node (ref "U401") (pin "53") (pinfunction "(CAP1.3/MISO1/MAT1.3)P0.18_53") (pintype "bidirectional"))
    )
    (net (code "61") (name "unconnected-(U401-(CTS1{slash}CAP1.1{slash}SCL1)P0.11-Pad37)") (class "Default")
      (node (ref "U401") (pin "37") (pinfunction "(CTS1/CAP1.1/SCL1)P0.11_37") (pintype "bidirectional"))
    )
    (net (code "62") (name "unconnected-(U401-(DTR1{slash}MAT1.1{slash}AD1.4)P0.13-Pad39)") (class "Default")
      (node (ref "U401") (pin "39") (pinfunction "(DTR1/MAT1.1/AD1.4)P0.13_39") (pintype "bidirectional"))
    )
    (net (code "63") (name "unconnected-(U401-(MAT1.2{slash}MOSI1{slash}CAP1.2)P0.19-Pad54)") (class "Default")
      (node (ref "U401") (pin "54") (pinfunction "(MAT1.2/MOSI1/CAP1.2)P0.19_54") (pintype "bidirectional"))
    )
    (net (code "64") (name "unconnected-(U401-(MAT1.3{slash}SSEL1{slash}EINT3)P0.20-Pad55)") (class "Default")
      (node (ref "U401") (pin "55") (pinfunction "(MAT1.3/SSEL1/EINT3)P0.20_55") (pintype "bidirectional"))
    )
    (net (code "65") (name "unconnected-(U401-(RTS1{slash}CAP1.0{slash}AD1.2)P0.10-Pad35)") (class "Default")
      (node (ref "U401") (pin "35") (pinfunction "(RTS1/CAP1.0/AD1.2)P0.10_35") (pintype "bidirectional"))
    )
    (net (code "66") (name "unconnected-(U401-P1.16(TRACEPKT0)-Pad16)") (class "Default")
      (node (ref "U401") (pin "16") (pinfunction "P1.16(TRACEPKT0)_16") (pintype "bidirectional"))
    )
    (net (code "67") (name "unconnected-(U401-P1.17(TRACEPKT1)-Pad12)") (class "Default")
      (node (ref "U401") (pin "12") (pinfunction "P1.17(TRACEPKT1)_12") (pintype "bidirectional"))
    )
    (net (code "68") (name "unconnected-(U401-P1.18(TRACEPKT2)-Pad8)") (class "Default")
      (node (ref "U401") (pin "8") (pinfunction "P1.18(TRACEPKT2)_8") (pintype "bidirectional"))
    )
    (net (code "69") (name "unconnected-(U401-P1.19(TRACEPKT3)-Pad4)") (class "Default")
      (node (ref "U401") (pin "4") (pinfunction "P1.19(TRACEPKT3)_4") (pintype "bidirectional"))
    )
    (net (code "70") (name "unconnected-(U401-P1.20(TRACESYNC)-Pad48)") (class "Default")
      (node (ref "U401") (pin "48") (pinfunction "P1.20(TRACESYNC)_48") (pintype "bidirectional"))
    )
    (net (code "71") (name "unconnected-(U401-P1.21(PIPESTAT0)-Pad44)") (class "Default")
      (node (ref "U401") (pin "44") (pinfunction "P1.21(PIPESTAT0)_44") (pintype "bidirectional"))
    )
    (net (code "72") (name "unconnected-(U401-P1.22(PIPESTAT1)-Pad40)") (class "Default")
      (node (ref "U401") (pin "40") (pinfunction "P1.22(PIPESTAT1)_40") (pintype "bidirectional"))
    )
    (net (code "73") (name "unconnected-(U401-P1.23(PIPESTAT2)-Pad36)") (class "Default")
      (node (ref "U401") (pin "36") (pinfunction "P1.23(PIPESTAT2)_36") (pintype "bidirectional"))
    )
    (net (code "74") (name "unconnected-(U401-P1.24(TRACECLK)-Pad32)") (class "Default")
      (node (ref "U401") (pin "32") (pinfunction "P1.24(TRACECLK)_32") (pintype "bidirectional"))
    )
    (net (code "75") (name "unconnected-(U401-P1.25(EXTIN0)-Pad28)") (class "Default")
      (node (ref "U401") (pin "28") (pinfunction "P1.25(EXTIN0)_28") (pintype "bidirectional"))
    )
    (net (code "76") (name "unconnected-(U401-P1.26(RTCK)-Pad24)") (class "Default")
      (node (ref "U401") (pin "24") (pinfunction "P1.26(RTCK)_24") (pintype "bidirectional"))
    )
    (net (code "77") (name "unconnected-(U401-P1.27(TDO)-Pad64)") (class "Default")
      (node (ref "U401") (pin "64") (pinfunction "P1.27(TDO)_64") (pintype "bidirectional"))
    )
    (net (code "78") (name "unconnected-(U401-P1.28(TDI)-Pad60)") (class "Default")
      (node (ref "U401") (pin "60") (pinfunction "P1.28(TDI)_60") (pintype "bidirectional"))
    )
    (net (code "79") (name "unconnected-(U401-P1.29(TCK)-Pad56)") (class "Default")
      (node (ref "U401") (pin "56") (pinfunction "P1.29(TCK)_56") (pintype "bidirectional"))
    )
    (net (code "80") (name "unconnected-(U401-P1.30(TMS)-Pad52)") (class "Default")
      (node (ref "U401") (pin "52") (pinfunction "P1.30(TMS)_52") (pintype "bidirectional"))
    )
    (net (code "81") (name "unconnected-(U401-P1.31({slash}TRST)-Pad20)") (class "Default")
      (node (ref "U401") (pin "20") (pinfunction "P1.31(/TRST)_20") (pintype "bidirectional"))
    )
    (net (code "82") (name "unconnected-(U401-RTXC2-Pad5)") (class "Default")
      (node (ref "U401") (pin "5") (pinfunction "RTXC2_5") (pintype "output"))
    )
    (net (code "83") (name "unconnected-(U601-CLKOUT-Pad22)") (class "Default")
      (node (ref "U601") (pin "22") (pinfunction "CLKOUT_22") (pintype "bidirectional"))
    )
    (net (code "84") (name "unconnected-(U601-ES_CL-Pad7)") (class "Default")
      (node (ref "U601") (pin "7") (pinfunction "ES_CL_7") (pintype "bidirectional"))
    )
    (net (code "85") (name "unconnected-(U601-ES_DA-Pad6)") (class "Default")
      (node (ref "U601") (pin "6") (pinfunction "ES_DA_6") (pintype "bidirectional"))
    )
    (net (code "86") (name "unconnected-(U902-INT1-Pad8)") (class "Default")
      (node (ref "U902") (pin "8") (pinfunction "INT1_8") (pintype "output"))
    )
    (net (code "87") (name "unconnected-(U902-INT2-Pad9)") (class "Default")
      (node (ref "U902") (pin "9") (pinfunction "INT2_9") (pintype "output"))
    )
  )
)
